# CAN_Interface.net
KiCad netlist of a schematic drawn in Altium Designer
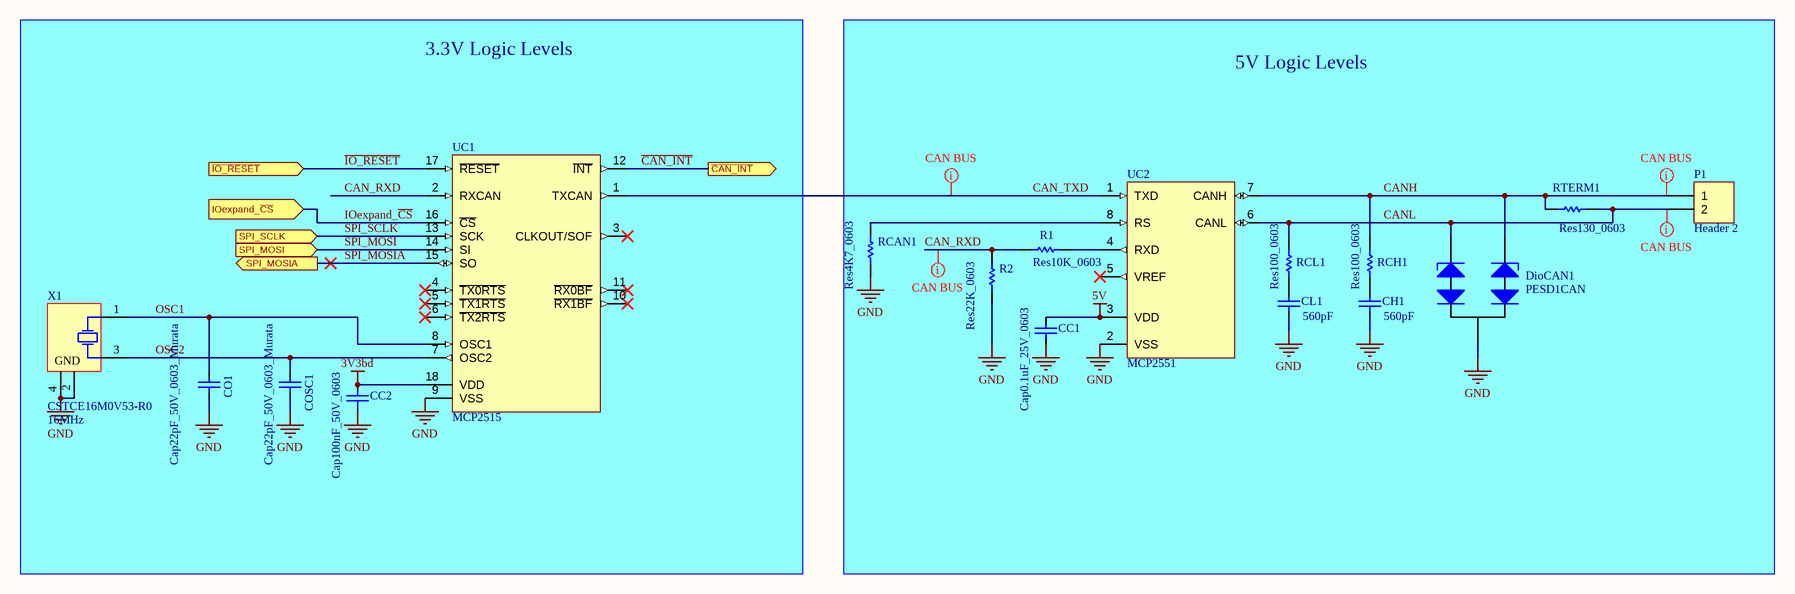
[diagram p0: CAN_Interface.SchDoc]

(export (version "E")
  (design (tool "Eeschema 10.0.6"))
  (components
    (comp (ref "CC1")
      (value "Cap0.1uF_25V_0603")
      (footprint "0603C_L")
      (libsource (lib "Advanced] Training Course - A365") (part "CAP General"))
    )
    (comp (ref "CC2")
      (value "Cap100nF_50V_0603")
      (footprint "0603C_L")
      (libsource (lib "Advanced] Training Course - A365") (part "CAP General"))
    )
    (comp (ref "CH1")
      (value "560pF")
      (footprint "0603C_L")
      (description "560pF 25V 0603")
      (fields (field (name "Comment") "CAP General"))
      (libsource (lib "Advanced] Training Course - A365") (part "CAP General"))
    )
    (comp (ref "CL1")
      (value "560pF")
      (footprint "0603C_L")
      (description "560pF 25V 0603")
      (fields (field (name "Comment") "CAP General"))
      (libsource (lib "Advanced] Training Course - A365") (part "CAP General"))
    )
    (comp (ref "CO1")
      (value "Cap22pF_50V_0603_Murata")
      (footprint "0603C_L")
      (fields (field (name "TOLERANCE") "5%"))
      (libsource (lib "Advanced] Training Course - A365") (part "CAP General"))
    )
    (comp (ref "COSC1")
      (value "Cap22pF_50V_0603_Murata")
      (footprint "0603C_L")
      (fields (field (name "TOLERANCE") "5%"))
      (libsource (lib "Advanced] Training Course - A365") (part "CAP General"))
    )
    (comp (ref "DioCAN1")
      (value "PESD1CAN")
      (footprint "SOT323")
      (description "Trans Voltage Suppressor Diode, 150W, 24V V(RWM), Bidirectional, 2 Element, Silicon")
      (fields (field (name "MANUFACTURER") "Nexperia USA Inc.") (field (name "SOURCE") "WCT.SchLib"))
      (libsource (lib "Advanced] Training Course - A365") (part "PESD1CAN"))
    )
    (comp (ref "P1")
      (value "Header 2")
      (footprint "HDR1X2")
      (description "Header, 2-Pin")
      (fields (field (name "PUBLISHER") "Altium Limited") (field (name "SOURCE") "WCT.SchLib"))
      (libsource (lib "Advanced] Training Course - A365") (part "Header 2"))
    )
    (comp (ref "R1")
      (value "Res10K_0603")
      (footprint "0603_L")
      (fields
        (field (name "MANUFACTURER") "Panasonic Electronic Components")
        (field (name "MANUFACTURER PART NUMBER") "ERJ-3GEYJ102V")
        (field (name "TOLERANCE") "5%")
        (field (name "SOURCE") "WCT.SchLib")
      )
      (libsource (lib "Advanced] Training Course - A365") (part "Resistor General"))
    )
    (comp (ref "R2")
      (value "Res22K_0603")
      (footprint "0603_L")
      (description "RES22K 0.5% 0603")
      (fields
        (field (name "MANUFACTURER") "Yageo")
        (field (name "MANUFACTURER PART NUMBER") "RT0603DRD0722KL")
        (field (name "SOURCE") "WCT.SchLib")
      )
      (libsource (lib "Advanced] Training Course - A365") (part "Resistor General"))
    )
    (comp (ref "RCAN1")
      (value "Res4K7_0603")
      (footprint "0603_L")
      (fields
        (field (name "MANUFACTURER") "Yageo")
        (field (name "TOLERANCE") "0.5%")
        (field (name "SOURCE") "WCT.SchLib")
      )
      (libsource (lib "Advanced] Training Course - A365") (part "Resistor General"))
    )
    (comp (ref "RCH1")
      (value "Res100_0603")
      (footprint "0603_L")
      (fields
        (field (name "MANUFACTURER") "Panasonic Electronic Components")
        (field (name "TOLERANCE") "5%")
        (field (name "SOURCE") "WCT.SchLib")
      )
      (libsource (lib "Advanced] Training Course - A365") (part "Resistor General"))
    )
    (comp (ref "RCL1")
      (value "Res100_0603")
      (footprint "0603_L")
      (fields
        (field (name "MANUFACTURER") "Panasonic Electronic Components")
        (field (name "TOLERANCE") "5%")
        (field (name "SOURCE") "WCT.SchLib")
      )
      (libsource (lib "Advanced] Training Course - A365") (part "Resistor General"))
    )
    (comp (ref "RTERM1")
      (value "Res130_0603")
      (footprint "0603_L")
      (fields
        (field (name "MANUFACTURER") "Panasonic Electronic Components")
        (field (name "TOLERANCE") "5%")
        (field (name "SOURCE") "WCT.SchLib")
      )
      (libsource (lib "Advanced] Training Course - A365") (part "Resistor General"))
    )
    (comp (ref "UC1")
      (value "MCP2515")
      (footprint "SOIC-SO18_M")
      (description "Stand-Alone CAN Controller With SPI Interface, 18-Pin SOIC, Extended Temperature")
      (fields
        (field (name "MANUFACTURER") "Microchip")
        (field (name "MANUFACTURER PART NUMBER") "MCP2515-E/SO")
        (field (name "AVAILABLE PREVIEW IMAGES") "2D")
        (field (name "SOURCE") "WCT.SchLib")
      )
      (libsource (lib "Advanced] Training Course - A365") (part "MCP2515"))
    )
    (comp (ref "UC2")
      (value "MCP2551")
      (footprint "SOIC-SN8_N")
      (description "High-Speed CAN Transceiver, 8-Pin SOIC, Extended Temperature")
      (fields
        (field (name "MANUFACTURER") "Microchip")
        (field (name "MANUFACTURER PART NUMBER") "MCP2551-E/SN")
        (field (name "AVAILABLE PREVIEW IMAGES") "2D")
        (field (name "SOURCE") "WCT.SchLib")
      )
      (libsource (lib "Advanced] Training Course - A365") (part "MCP2551"))
    )
    (comp (ref "X1")
      (value "CSTCE16M0V53-R0")
      (footprint "FP-ABM8-MFG")
      (description "Crystal 16MHz ±20ppm 18pF SMD-4 3.2mm x 2.5mm CSTCE16M0V53-R0 ABM8-16.000MHZ-B2-T")
      (fields
        (field (name "TOLERANCE") "20ppm")
        (field (name "FREQUENCY") "16MHz")
        (field (name "SOURCE") "WCT.SchLib")
      )
      (libsource (lib " Advanced] Training Course - A365") (part "Crystal 4Pin"))
    )
  )
  (nets
    (net (code "1") (name "/CANH") (class "Default")
      (node (ref "DioCAN1") (pin "1") (pinfunction "A_1") (pintype "passive"))
      (node (ref "P1") (pin "1") (pinfunction "1_1") (pintype "passive"))
      (node (ref "RCH1") (pin "2") (pinfunction "2_2") (pintype "passive"))
      (node (ref "RTERM1") (pin "2") (pinfunction "2_2") (pintype "passive"))
      (node (ref "UC2") (pin "7") (pinfunction "CANH_7") (pintype "bidirectional"))
    )
    (net (code "2") (name "/CANL") (class "Default")
      (node (ref "DioCAN1") (pin "2") (pinfunction "K_2") (pintype "passive"))
      (node (ref "P1") (pin "2") (pinfunction "2_2") (pintype "passive"))
      (node (ref "RCL1") (pin "2") (pinfunction "2_2") (pintype "passive"))
      (node (ref "RTERM1") (pin "1") (pinfunction "1_1") (pintype "passive"))
      (node (ref "UC2") (pin "6") (pinfunction "CANL_6") (pintype "bidirectional"))
    )
    (net (code "3") (name "/CAN_INT") (class "Default")
      (node (ref "UC1") (pin "12") (pinfunction "~{INT}_12") (pintype "output"))
    )
    (net (code "4") (name "/CAN_RXD") (class "Default")
      (node (ref "R1") (pin "2") (pinfunction "2_2") (pintype "passive"))
      (node (ref "R2") (pin "2") (pinfunction "2_2") (pintype "passive"))
      (node (ref "UC1") (pin "2") (pinfunction "RXCAN_2") (pintype "input"))
    )
    (net (code "5") (name "/CAN_TXD") (class "Default")
      (node (ref "UC1") (pin "1") (pinfunction "TXCAN_1") (pintype "output"))
      (node (ref "UC2") (pin "1") (pinfunction "TXD_1") (pintype "input"))
    )
    (net (code "6") (name "/IO_RESET") (class "Default")
      (node (ref "UC1") (pin "17") (pinfunction "~{RESET}_17") (pintype "input"))
    )
    (net (code "7") (name "/IOexpand_~{CS}") (class "Default")
      (node (ref "UC1") (pin "16") (pinfunction "~{CS}_16") (pintype "input"))
    )
    (net (code "8") (name "/OSC1") (class "Default")
      (node (ref "CO1") (pin "2") (pinfunction "2_2") (pintype "passive"))
      (node (ref "UC1") (pin "8") (pinfunction "OSC1_8") (pintype "input"))
      (node (ref "X1") (pin "1") (pinfunction "1_1") (pintype "passive"))
    )
    (net (code "9") (name "/OSC2") (class "Default")
      (node (ref "COSC1") (pin "2") (pinfunction "2_2") (pintype "passive"))
      (node (ref "UC1") (pin "7") (pinfunction "OSC2_7") (pintype "output"))
      (node (ref "X1") (pin "3") (pinfunction "3_3") (pintype "passive"))
    )
    (net (code "10") (name "/SPI_MOSI") (class "Default")
      (node (ref "UC1") (pin "14") (pinfunction "SI_14") (pintype "input"))
    )
    (net (code "11") (name "/SPI_MOSIA") (class "Default")
      (node (ref "UC1") (pin "15") (pinfunction "SO_15") (pintype "bidirectional"))
    )
    (net (code "12") (name "/SPI_SCLK") (class "Default")
      (node (ref "UC1") (pin "13") (pinfunction "SCK_13") (pintype "input"))
    )
    (net (code "13") (name "3V3bd") (class "Default")
      (node (ref "CC2") (pin "2") (pinfunction "2_2") (pintype "passive"))
      (node (ref "UC1") (pin "18") (pinfunction "VDD_18") (pintype "power_in"))
    )
    (net (code "14") (name "5V") (class "Default")
      (node (ref "CC1") (pin "2") (pinfunction "2_2") (pintype "passive"))
      (node (ref "UC2") (pin "3") (pinfunction "VDD_3") (pintype "power_in"))
    )
    (net (code "15") (name "GND") (class "Default")
      (node (ref "CC1") (pin "1") (pinfunction "1_1") (pintype "passive"))
      (node (ref "CC2") (pin "1") (pinfunction "1_1") (pintype "passive"))
      (node (ref "CH1") (pin "2") (pinfunction "2_2") (pintype "passive"))
      (node (ref "CL1") (pin "1") (pinfunction "1_1") (pintype "passive"))
      (node (ref "CO1") (pin "1") (pinfunction "1_1") (pintype "passive"))
      (node (ref "COSC1") (pin "1") (pinfunction "1_1") (pintype "passive"))
      (node (ref "DioCAN1") (pin "3") (pinfunction "3_3") (pintype "passive"))
      (node (ref "R2") (pin "1") (pinfunction "1_1") (pintype "passive"))
      (node (ref "RCAN1") (pin "1") (pinfunction "1_1") (pintype "passive"))
      (node (ref "UC1") (pin "9") (pinfunction "VSS_9") (pintype "power_in"))
      (node (ref "UC2") (pin "2") (pinfunction "VSS_2") (pintype "power_in"))
      (node (ref "X1") (pin "2") (pinfunction "GND_2") (pintype "power_in"))
      (node (ref "X1") (pin "4") (pinfunction "GND_4") (pintype "power_in"))
    )
    (net (code "16") (name "Net-(CH1-Pad1)") (class "Default")
      (node (ref "CH1") (pin "1") (pinfunction "1_1") (pintype "passive"))
      (node (ref "RCH1") (pin "1") (pinfunction "1_1") (pintype "passive"))
    )
    (net (code "17") (name "Net-(CL1-Pad2)") (class "Default")
      (node (ref "CL1") (pin "2") (pinfunction "2_2") (pintype "passive"))
      (node (ref "RCL1") (pin "1") (pinfunction "1_1") (pintype "passive"))
    )
    (net (code "18") (name "Net-(UC2-RS)") (class "Default")
      (node (ref "RCAN1") (pin "2") (pinfunction "2_2") (pintype "passive"))
      (node (ref "UC2") (pin "8") (pinfunction "RS_8") (pintype "input"))
    )
    (net (code "19") (name "Net-(UC2-RXD)") (class "Default")
      (node (ref "R1") (pin "1") (pinfunction "1_1") (pintype "passive"))
      (node (ref "UC2") (pin "4") (pinfunction "RXD_4") (pintype "output"))
    )
    (net (code "20") (name "unconnected-(UC1-CLKOUT{slash}SOF-Pad3)") (class "Default")
      (node (ref "UC1") (pin "3") (pinfunction "CLKOUT/SOF_3") (pintype "output+no_connect"))
    )
    (net (code "21") (name "unconnected-(UC1-~{RX0BF}-Pad11)") (class "Default")
      (node (ref "UC1") (pin "11") (pinfunction "~{RX0BF}_11") (pintype "output+no_connect"))
    )
    (net (code "22") (name "unconnected-(UC1-~{RX1BF}-Pad10)") (class "Default")
      (node (ref "UC1") (pin "10") (pinfunction "~{RX1BF}_10") (pintype "output+no_connect"))
    )
    (net (code "23") (name "unconnected-(UC1-~{TX0RTS}-Pad4)") (class "Default")
      (node (ref "UC1") (pin "4") (pinfunction "~{TX0RTS}_4") (pintype "input+no_connect"))
    )
    (net (code "24") (name "unconnected-(UC1-~{TX1RTS}-Pad5)") (class "Default")
      (node (ref "UC1") (pin "5") (pinfunction "~{TX1RTS}_5") (pintype "input+no_connect"))
    )
    (net (code "25") (name "unconnected-(UC1-~{TX2RTS}-Pad6)") (class "Default")
      (node (ref "UC1") (pin "6") (pinfunction "~{TX2RTS}_6") (pintype "input+no_connect"))
    )
    (net (code "26") (name "unconnected-(UC2-VREF-Pad5)") (class "Default")
      (node (ref "UC2") (pin "5") (pinfunction "VREF_5") (pintype "output+no_connect"))
    )
  )
)
